# LR2051-902-sensor-board.net
KiCad netlist of a schematic drawn in EAGLE
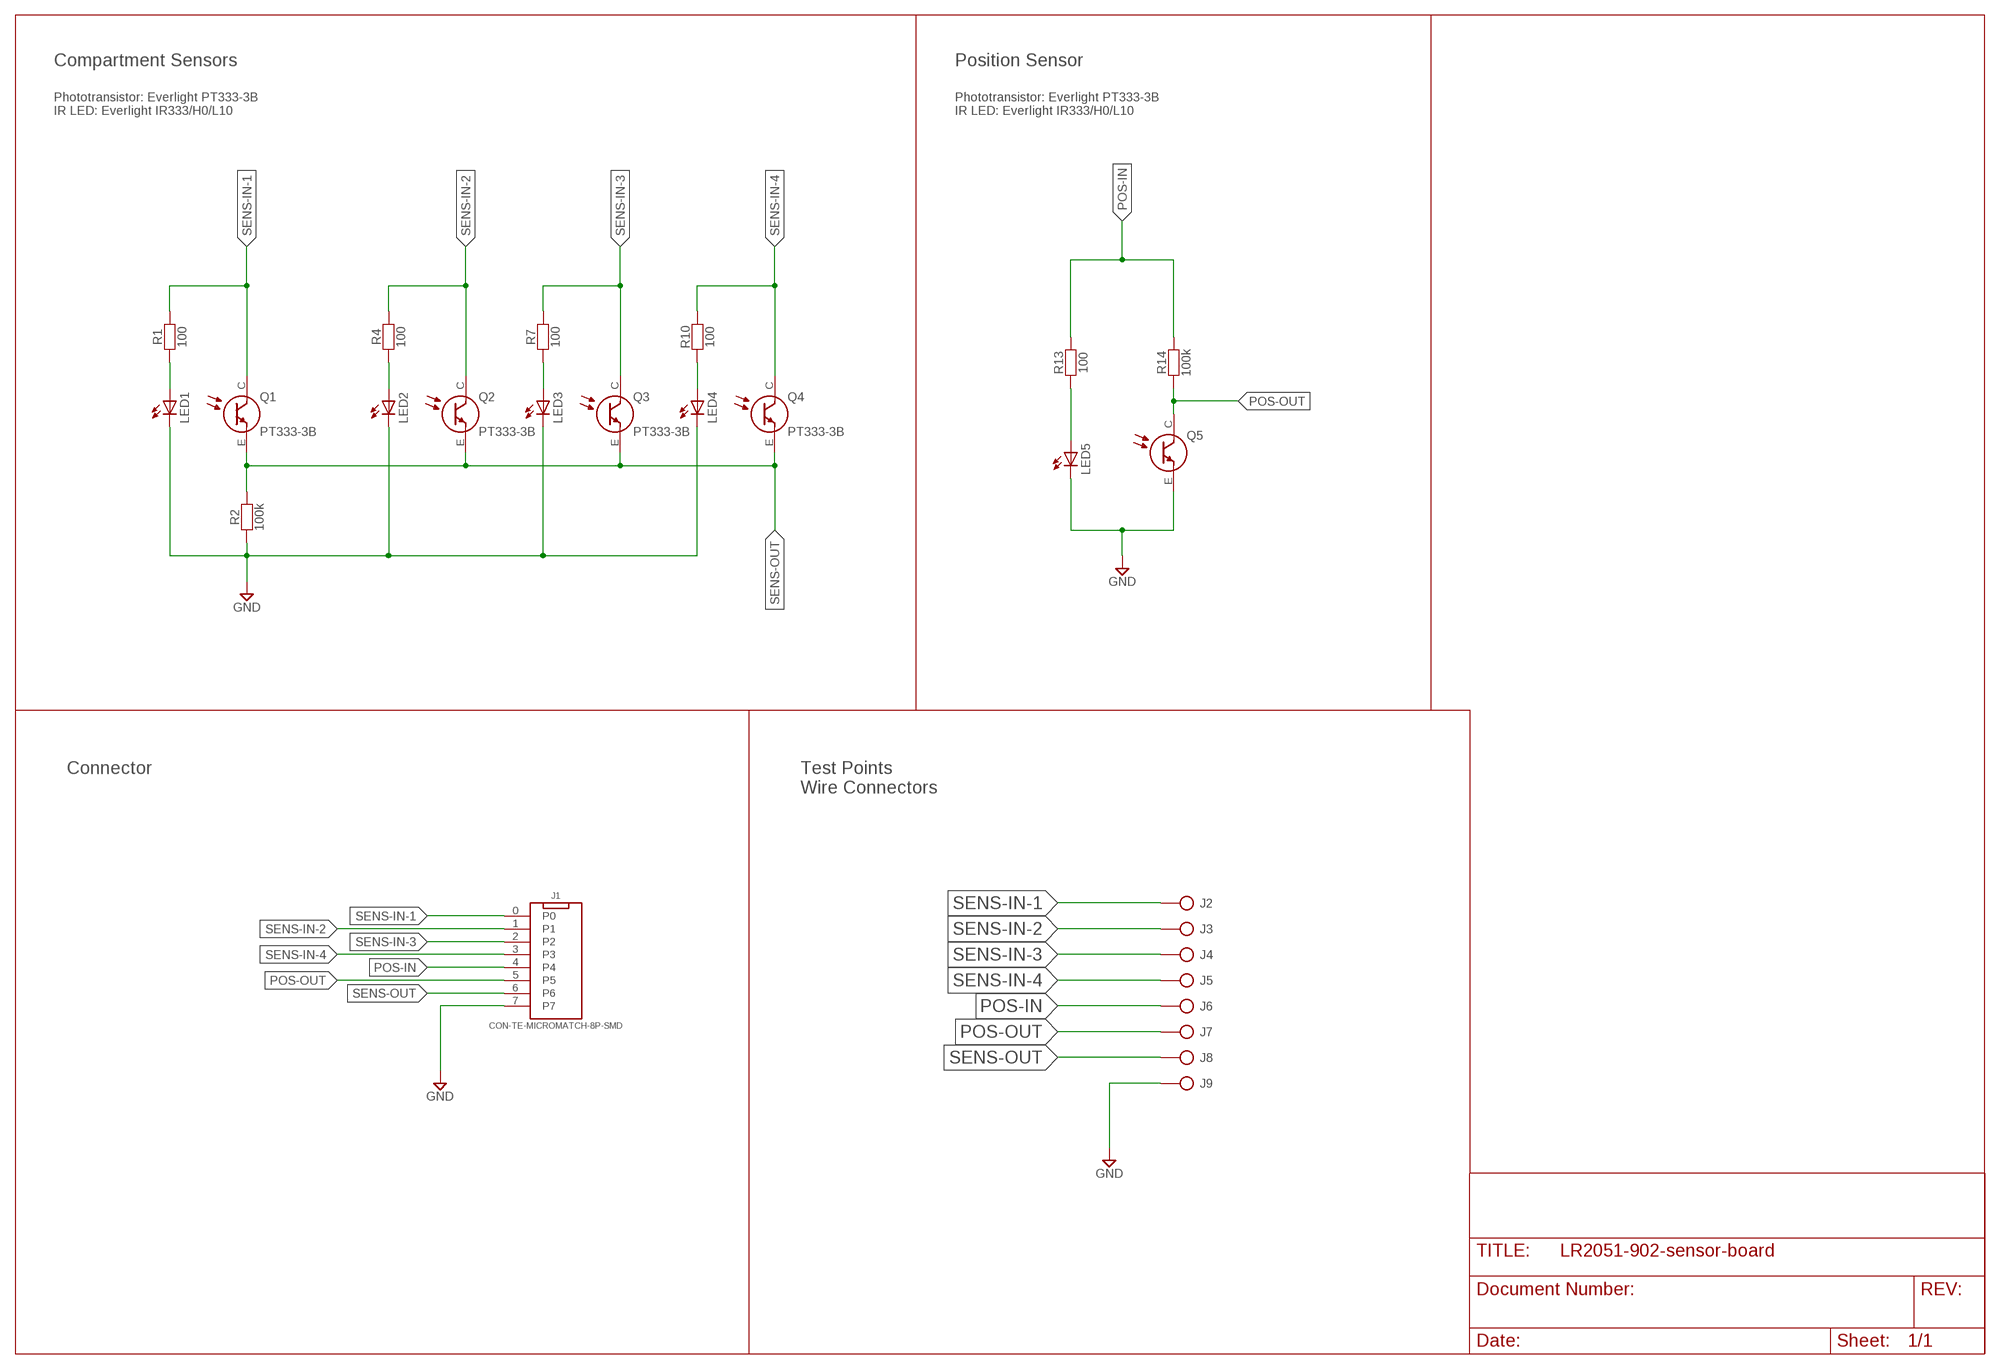
[diagram p0: schematic, sheet 1]

(export (version "E")
  (design (tool "Eeschema 10.0.6"))
  (components
    (comp (ref "J1")
      (value "CON-TE-MICROMATCH-8P-SMD")
      (footprint "eagle-import:CON-TE-MICROMATCH-2178711-8")
      (libsource (lib "eagle-import") (part "CON-TE-MICROMATCH-8P-SMD"))
    )
    (comp (ref "J2")
      (value "CON-HOLE-D0.9")
      (footprint "eagle-import:CON-HOLE-D0.9")
      (libsource (lib "eagle-import") (part "CON-HOLE-D0.9"))
    )
    (comp (ref "J3")
      (value "CON-HOLE-D0.9")
      (footprint "eagle-import:CON-HOLE-D0.9")
      (libsource (lib "eagle-import") (part "CON-HOLE-D0.9"))
    )
    (comp (ref "J4")
      (value "CON-HOLE-D0.9")
      (footprint "eagle-import:CON-HOLE-D0.9")
      (libsource (lib "eagle-import") (part "CON-HOLE-D0.9"))
    )
    (comp (ref "J5")
      (value "CON-HOLE-D0.9")
      (footprint "eagle-import:CON-HOLE-D0.9")
      (libsource (lib "eagle-import") (part "CON-HOLE-D0.9"))
    )
    (comp (ref "J6")
      (value "CON-HOLE-D0.9")
      (footprint "eagle-import:CON-HOLE-D0.9")
      (libsource (lib "eagle-import") (part "CON-HOLE-D0.9"))
    )
    (comp (ref "J7")
      (value "CON-HOLE-D0.9")
      (footprint "eagle-import:CON-HOLE-D0.9")
      (libsource (lib "eagle-import") (part "CON-HOLE-D0.9"))
    )
    (comp (ref "J8")
      (value "CON-HOLE-D0.9")
      (footprint "eagle-import:CON-HOLE-D0.9")
      (libsource (lib "eagle-import") (part "CON-HOLE-D0.9"))
    )
    (comp (ref "J9")
      (value "CON-HOLE-D0.9")
      (footprint "eagle-import:CON-HOLE-D0.9")
      (libsource (lib "eagle-import") (part "CON-HOLE-D0.9"))
    )
    (comp (ref "LED1")
      (value "LED5MM")
      (footprint "eagle-import:LED5MM")
      (libsource (lib "eagle-import") (part "LED5MM"))
    )
    (comp (ref "LED2")
      (value "LED5MM")
      (footprint "eagle-import:LED5MM")
      (libsource (lib "eagle-import") (part "LED5MM"))
    )
    (comp (ref "LED3")
      (value "LED5MM")
      (footprint "eagle-import:LED5MM")
      (libsource (lib "eagle-import") (part "LED5MM"))
    )
    (comp (ref "LED4")
      (value "LED5MM")
      (footprint "eagle-import:LED5MM")
      (libsource (lib "eagle-import") (part "LED5MM"))
    )
    (comp (ref "LED5")
      (value "LED5MM")
      (footprint "eagle-import:LED5MM")
      (libsource (lib "eagle-import") (part "LED5MM"))
    )
    (comp (ref "Q1")
      (value "PT333-3B")
      (footprint "eagle-import:Q-PHOTO-2P-TH-5MM")
      (libsource (lib "eagle-import") (part "Q-PHOTO-TH-5MM"))
    )
    (comp (ref "Q2")
      (value "PT333-3B")
      (footprint "eagle-import:Q-PHOTO-2P-TH-5MM")
      (libsource (lib "eagle-import") (part "Q-PHOTO-TH-5MM"))
    )
    (comp (ref "Q3")
      (value "PT333-3B")
      (footprint "eagle-import:Q-PHOTO-2P-TH-5MM")
      (libsource (lib "eagle-import") (part "Q-PHOTO-TH-5MM"))
    )
    (comp (ref "Q4")
      (value "PT333-3B")
      (footprint "eagle-import:Q-PHOTO-2P-TH-5MM")
      (libsource (lib "eagle-import") (part "Q-PHOTO-TH-5MM"))
    )
    (comp (ref "Q5")
      (value "Q-PHOTO-TH-5MM")
      (footprint "eagle-import:Q-PHOTO-2P-TH-5MM")
      (libsource (lib "eagle-import") (part "Q-PHOTO-TH-5MM"))
    )
    (comp (ref "R1")
      (value "100")
      (footprint "eagle-import:R-0805-HANDSOLDER")
      (libsource (lib "eagle-import") (part "R-0805-HANDSOLDER"))
    )
    (comp (ref "R2")
      (value "100k")
      (footprint "eagle-import:R-0805-HANDSOLDER")
      (libsource (lib "eagle-import") (part "R-0805-HANDSOLDER"))
    )
    (comp (ref "R4")
      (value "100")
      (footprint "eagle-import:R-0805-HANDSOLDER")
      (libsource (lib "eagle-import") (part "R-0805-HANDSOLDER"))
    )
    (comp (ref "R7")
      (value "100")
      (footprint "eagle-import:R-0805-HANDSOLDER")
      (libsource (lib "eagle-import") (part "R-0805-HANDSOLDER"))
    )
    (comp (ref "R10")
      (value "100")
      (footprint "eagle-import:R-0805-HANDSOLDER")
      (libsource (lib "eagle-import") (part "R-0805-HANDSOLDER"))
    )
    (comp (ref "R13")
      (value "100")
      (footprint "eagle-import:R-0805-HANDSOLDER")
      (libsource (lib "eagle-import") (part "R-0805-HANDSOLDER"))
    )
    (comp (ref "R14")
      (value "100k")
      (footprint "eagle-import:R-0805-HANDSOLDER")
      (libsource (lib "eagle-import") (part "R-0805-HANDSOLDER"))
    )
  )
  (nets
    (net (code "1") (name "GND") (class "Default")
      (node (ref "J1") (pin "7") (pinfunction "P7_7") (pintype "bidirectional"))
      (node (ref "J9") (pin "1") (pinfunction "1_1") (pintype "passive"))
      (node (ref "LED1") (pin "K") (pinfunction "C_K") (pintype "passive"))
      (node (ref "LED2") (pin "K") (pinfunction "C_K") (pintype "passive"))
      (node (ref "LED3") (pin "K") (pinfunction "C_K") (pintype "passive"))
      (node (ref "LED4") (pin "K") (pinfunction "C_K") (pintype "passive"))
      (node (ref "LED5") (pin "K") (pinfunction "C_K") (pintype "passive"))
      (node (ref "Q5") (pin "E") (pinfunction "E_E") (pintype "passive"))
      (node (ref "R2") (pin "1") (pinfunction "P1_1") (pintype "passive"))
    )
    (net (code "2") (name "Net-(R1-P1)") (class "Default")
      (node (ref "LED1") (pin "A") (pinfunction "A_A") (pintype "passive"))
      (node (ref "R1") (pin "1") (pinfunction "P1_1") (pintype "passive"))
    )
    (net (code "3") (name "Net-(R4-P1)") (class "Default")
      (node (ref "LED2") (pin "A") (pinfunction "A_A") (pintype "passive"))
      (node (ref "R4") (pin "1") (pinfunction "P1_1") (pintype "passive"))
    )
    (net (code "4") (name "Net-(R7-P1)") (class "Default")
      (node (ref "LED3") (pin "A") (pinfunction "A_A") (pintype "passive"))
      (node (ref "R7") (pin "1") (pinfunction "P1_1") (pintype "passive"))
    )
    (net (code "5") (name "Net-(R10-P1)") (class "Default")
      (node (ref "LED4") (pin "A") (pinfunction "A_A") (pintype "passive"))
      (node (ref "R10") (pin "1") (pinfunction "P1_1") (pintype "passive"))
    )
    (net (code "6") (name "Net-(R13-P1)") (class "Default")
      (node (ref "LED5") (pin "A") (pinfunction "A_A") (pintype "passive"))
      (node (ref "R13") (pin "1") (pinfunction "P1_1") (pintype "passive"))
    )
    (net (code "7") (name "POS-IN") (class "Default")
      (node (ref "J1") (pin "4") (pinfunction "P4_4") (pintype "bidirectional"))
      (node (ref "J6") (pin "1") (pinfunction "1_1") (pintype "passive"))
      (node (ref "R13") (pin "2") (pinfunction "P2_2") (pintype "passive"))
      (node (ref "R14") (pin "2") (pinfunction "P2_2") (pintype "passive"))
    )
    (net (code "8") (name "POS-OUT") (class "Default")
      (node (ref "J1") (pin "5") (pinfunction "P5_5") (pintype "bidirectional"))
      (node (ref "J7") (pin "1") (pinfunction "1_1") (pintype "passive"))
      (node (ref "Q5") (pin "C") (pinfunction "C_C") (pintype "passive"))
      (node (ref "R14") (pin "1") (pinfunction "P1_1") (pintype "passive"))
    )
    (net (code "9") (name "SENS-IN-1") (class "Default")
      (node (ref "J1") (pin "0") (pinfunction "P0_0") (pintype "bidirectional"))
      (node (ref "J2") (pin "1") (pinfunction "1_1") (pintype "passive"))
      (node (ref "Q1") (pin "C") (pinfunction "C_C") (pintype "passive"))
      (node (ref "R1") (pin "2") (pinfunction "P2_2") (pintype "passive"))
    )
    (net (code "10") (name "SENS-IN-2") (class "Default")
      (node (ref "J1") (pin "1") (pinfunction "P1_1") (pintype "bidirectional"))
      (node (ref "J3") (pin "1") (pinfunction "1_1") (pintype "passive"))
      (node (ref "Q2") (pin "C") (pinfunction "C_C") (pintype "passive"))
      (node (ref "R4") (pin "2") (pinfunction "P2_2") (pintype "passive"))
    )
    (net (code "11") (name "SENS-IN-3") (class "Default")
      (node (ref "J1") (pin "2") (pinfunction "P2_2") (pintype "bidirectional"))
      (node (ref "J4") (pin "1") (pinfunction "1_1") (pintype "passive"))
      (node (ref "Q3") (pin "C") (pinfunction "C_C") (pintype "passive"))
      (node (ref "R7") (pin "2") (pinfunction "P2_2") (pintype "passive"))
    )
    (net (code "12") (name "SENS-IN-4") (class "Default")
      (node (ref "J1") (pin "3") (pinfunction "P3_3") (pintype "bidirectional"))
      (node (ref "J5") (pin "1") (pinfunction "1_1") (pintype "passive"))
      (node (ref "Q4") (pin "C") (pinfunction "C_C") (pintype "passive"))
      (node (ref "R10") (pin "2") (pinfunction "P2_2") (pintype "passive"))
    )
    (net (code "13") (name "SENS-OUT") (class "Default")
      (node (ref "J1") (pin "6") (pinfunction "P6_6") (pintype "bidirectional"))
      (node (ref "J8") (pin "1") (pinfunction "1_1") (pintype "passive"))
      (node (ref "Q1") (pin "E") (pinfunction "E_E") (pintype "passive"))
      (node (ref "Q2") (pin "E") (pinfunction "E_E") (pintype "passive"))
      (node (ref "Q3") (pin "E") (pinfunction "E_E") (pintype "passive"))
      (node (ref "Q4") (pin "E") (pinfunction "E_E") (pintype "passive"))
      (node (ref "R2") (pin "2") (pinfunction "P2_2") (pintype "passive"))
    )
  )
)
